# rtc_ds3231_shield.net
KiCad netlist of a schematic drawn in EAGLE
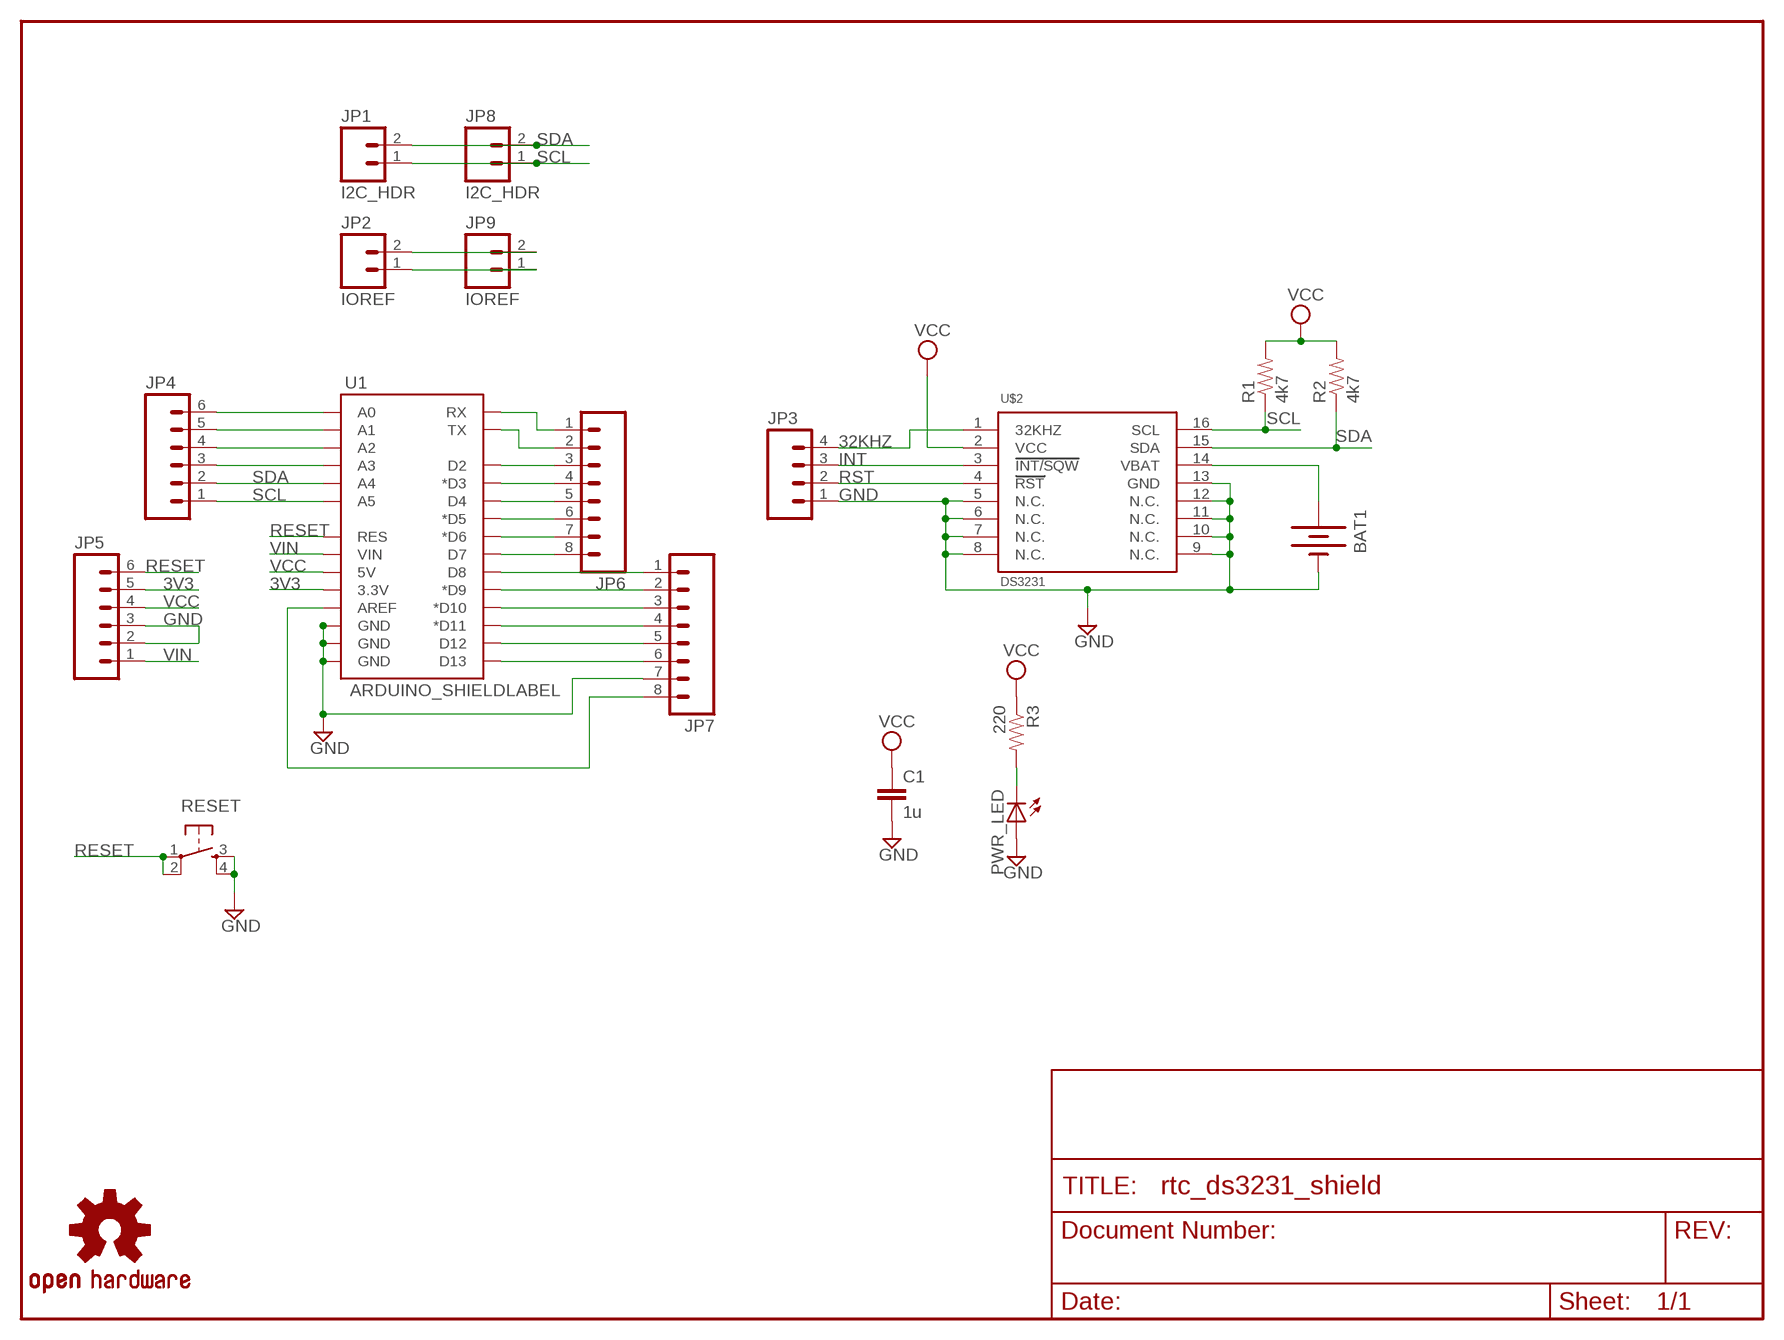
[diagram p0: schematic, sheet 1]

(export (version "E")
  (design (tool "Eeschema 10.0.6"))
  (components
    (comp (ref "BAT1")
      (value "BATTERY12MM")
      (footprint "eagle-import:BATTCON_12MM")
      (libsource (lib "eagle-import") (part "BATTERY12MM"))
    )
    (comp (ref "C1")
      (value "1u")
      (footprint "eagle-import:1206")
      (libsource (lib "eagle-import") (part "CAP1206"))
    )
    (comp (ref "JP1")
      (value "I2C_HDR")
      (footprint "eagle-import:1X02")
      (libsource (lib "eagle-import") (part "M02PTH"))
    )
    (comp (ref "JP2")
      (value "IOREF")
      (footprint "eagle-import:1X02")
      (libsource (lib "eagle-import") (part "M02PTH"))
    )
    (comp (ref "JP3")
      (value "M04PTH")
      (footprint "eagle-import:1X04")
      (libsource (lib "eagle-import") (part "M04PTH"))
    )
    (comp (ref "JP4")
      (value "M06SIP")
      (footprint "eagle-import:1X06")
      (libsource (lib "eagle-import") (part "M06SIP"))
    )
    (comp (ref "JP5")
      (value "M06SIP")
      (footprint "eagle-import:1X06")
      (libsource (lib "eagle-import") (part "M06SIP"))
    )
    (comp (ref "JP6")
      (value "M081X08")
      (footprint "eagle-import:1X08")
      (libsource (lib "eagle-import") (part "M081X08"))
    )
    (comp (ref "JP7")
      (value "M081X08")
      (footprint "eagle-import:1X08")
      (libsource (lib "eagle-import") (part "M081X08"))
    )
    (comp (ref "JP8")
      (value "I2C_HDR")
      (footprint "eagle-import:1X02")
      (libsource (lib "eagle-import") (part "M02PTH"))
    )
    (comp (ref "JP9")
      (value "IOREF")
      (footprint "eagle-import:1X02")
      (libsource (lib "eagle-import") (part "M02PTH"))
    )
    (comp (ref "PWR_LED")
      (value "LED1206")
      (footprint "eagle-import:LED-1206")
      (libsource (lib "eagle-import") (part "LED1206"))
    )
    (comp (ref "R1")
      (value "4k7")
      (footprint "eagle-import:1206")
      (libsource (lib "eagle-import") (part "RESISTOR1206"))
    )
    (comp (ref "R2")
      (value "4k7")
      (footprint "eagle-import:1206")
      (libsource (lib "eagle-import") (part "RESISTOR1206"))
    )
    (comp (ref "R3")
      (value "220")
      (footprint "eagle-import:1206")
      (libsource (lib "eagle-import") (part "RESISTOR1206"))
    )
    (comp (ref "RESET")
      (value "TAC_SWITCHSMD")
      (footprint "eagle-import:TACTILE_SWITCH_SMD")
      (libsource (lib "eagle-import") (part "TAC_SWITCHSMD"))
    )
    (comp (ref "U$2")
      (value "DS3231")
      (footprint "eagle-import:SO16L")
      (libsource (lib "eagle-import") (part "DS3231"))
    )
    (comp (ref "U$3")
      (value "OSHW-LOGOM")
      (footprint "eagle-import:OSHW-LOGO-M")
      (libsource (lib "eagle-import") (part "OSHW-LOGOM"))
    )
    (comp (ref "U1")
      (value "ARDUINO_SHIELDLABEL")
      (footprint "eagle-import:UNOR3_SHIELD")
      (libsource (lib "eagle-import") (part "ARDUINO_SHIELDLABEL"))
    )
  )
  (nets
    (net (code "1") (name "/3V3") (class "Default")
      (node (ref "JP5") (pin "5") (pinfunction "5_5") (pintype "passive"))
      (node (ref "U1") (pin "3.3V") (pinfunction "3.3V_3.3V") (pintype "bidirectional"))
    )
    (net (code "2") (name "/32KHZ") (class "Default")
      (node (ref "JP3") (pin "4") (pinfunction "4_4") (pintype "passive"))
      (node (ref "U$2") (pin "1") (pinfunction "32KHZ_1") (pintype "bidirectional"))
    )
    (net (code "3") (name "/INT") (class "Default")
      (node (ref "JP3") (pin "3") (pinfunction "3_3") (pintype "passive"))
      (node (ref "U$2") (pin "3") (pinfunction "INT/SQW_3") (pintype "bidirectional"))
    )
    (net (code "4") (name "/RESET") (class "Default")
      (node (ref "JP5") (pin "6") (pinfunction "6_6") (pintype "passive"))
      (node (ref "RESET") (pin "1") (pinfunction "1_1") (pintype "passive"))
      (node (ref "RESET") (pin "2") (pinfunction "2_2") (pintype "passive"))
      (node (ref "U1") (pin "RES") (pinfunction "RES_RES") (pintype "bidirectional"))
    )
    (net (code "5") (name "/RST") (class "Default")
      (node (ref "JP3") (pin "2") (pinfunction "2_2") (pintype "passive"))
      (node (ref "U$2") (pin "4") (pinfunction "RST_4") (pintype "bidirectional"))
    )
    (net (code "6") (name "/SCL") (class "Default")
      (node (ref "JP1") (pin "1") (pinfunction "1_1") (pintype "passive"))
      (node (ref "JP4") (pin "1") (pinfunction "1_1") (pintype "passive"))
      (node (ref "JP8") (pin "1") (pinfunction "1_1") (pintype "passive"))
      (node (ref "R1") (pin "1") (pinfunction "1_1") (pintype "passive"))
      (node (ref "U$2") (pin "16") (pinfunction "SCL_16") (pintype "bidirectional"))
      (node (ref "U1") (pin "A5") (pinfunction "A5_A5") (pintype "bidirectional"))
    )
    (net (code "7") (name "/SDA") (class "Default")
      (node (ref "JP1") (pin "2") (pinfunction "2_2") (pintype "passive"))
      (node (ref "JP4") (pin "2") (pinfunction "2_2") (pintype "passive"))
      (node (ref "JP8") (pin "2") (pinfunction "2_2") (pintype "passive"))
      (node (ref "R2") (pin "1") (pinfunction "1_1") (pintype "passive"))
      (node (ref "U$2") (pin "15") (pinfunction "SDA_15") (pintype "bidirectional"))
      (node (ref "U1") (pin "A4") (pinfunction "A4_A4") (pintype "bidirectional"))
    )
    (net (code "8") (name "/VIN") (class "Default")
      (node (ref "JP5") (pin "1") (pinfunction "1_1") (pintype "passive"))
      (node (ref "U1") (pin "VIN") (pinfunction "VIN_VIN") (pintype "bidirectional"))
    )
    (net (code "9") (name "GND") (class "Default")
      (node (ref "BAT1") (pin "GND") (pinfunction "-_GND") (pintype "power_in"))
      (node (ref "C1") (pin "2") (pinfunction "2_2") (pintype "passive"))
      (node (ref "JP3") (pin "1") (pinfunction "1_1") (pintype "passive"))
      (node (ref "JP5") (pin "2") (pinfunction "2_2") (pintype "passive"))
      (node (ref "JP5") (pin "3") (pinfunction "3_3") (pintype "passive"))
      (node (ref "JP7") (pin "7") (pinfunction "7_7") (pintype "passive"))
      (node (ref "PWR_LED") (pin "A") (pinfunction "A_A") (pintype "passive"))
      (node (ref "RESET") (pin "3") (pinfunction "3_3") (pintype "passive"))
      (node (ref "RESET") (pin "4") (pinfunction "4_4") (pintype "passive"))
      (node (ref "U$2") (pin "10") (pinfunction "N.C._10") (pintype "bidirectional"))
      (node (ref "U$2") (pin "11") (pinfunction "N.C._11") (pintype "bidirectional"))
      (node (ref "U$2") (pin "12") (pinfunction "N.C._12") (pintype "bidirectional"))
      (node (ref "U$2") (pin "13") (pinfunction "GND_13") (pintype "power_in"))
      (node (ref "U$2") (pin "5") (pinfunction "N.C._5") (pintype "bidirectional"))
      (node (ref "U$2") (pin "6") (pinfunction "N.C._6") (pintype "bidirectional"))
      (node (ref "U$2") (pin "7") (pinfunction "N.C._7") (pintype "bidirectional"))
      (node (ref "U$2") (pin "8") (pinfunction "N.C._8") (pintype "bidirectional"))
      (node (ref "U$2") (pin "9") (pinfunction "N.C._9") (pintype "bidirectional"))
      (node (ref "U1") (pin "GND@0") (pinfunction "GND_GND@0") (pintype "bidirectional"))
      (node (ref "U1") (pin "GND@1") (pinfunction "GND_GND@1") (pintype "bidirectional"))
      (node (ref "U1") (pin "GND@2") (pinfunction "GND_GND@2") (pintype "bidirectional"))
    )
    (net (code "10") (name "Net-(BAT1-+)") (class "Default")
      (node (ref "BAT1") (pin "PWR@2") (pinfunction "+_PWR@2") (pintype "power_in"))
      (node (ref "U$2") (pin "14") (pinfunction "VBAT_14") (pintype "power_in"))
    )
    (net (code "11") (name "Net-(JP2-Pad1)") (class "Default")
      (node (ref "JP2") (pin "1") (pinfunction "1_1") (pintype "passive"))
      (node (ref "JP9") (pin "1") (pinfunction "1_1") (pintype "passive"))
    )
    (net (code "12") (name "Net-(JP2-Pad2)") (class "Default")
      (node (ref "JP2") (pin "2") (pinfunction "2_2") (pintype "passive"))
      (node (ref "JP9") (pin "2") (pinfunction "2_2") (pintype "passive"))
    )
    (net (code "13") (name "Net-(JP4-Pad3)") (class "Default")
      (node (ref "JP4") (pin "3") (pinfunction "3_3") (pintype "passive"))
      (node (ref "U1") (pin "A3") (pinfunction "A3_A3") (pintype "bidirectional"))
    )
    (net (code "14") (name "Net-(JP4-Pad4)") (class "Default")
      (node (ref "JP4") (pin "4") (pinfunction "4_4") (pintype "passive"))
      (node (ref "U1") (pin "A2") (pinfunction "A2_A2") (pintype "bidirectional"))
    )
    (net (code "15") (name "Net-(JP4-Pad5)") (class "Default")
      (node (ref "JP4") (pin "5") (pinfunction "5_5") (pintype "passive"))
      (node (ref "U1") (pin "A1") (pinfunction "A1_A1") (pintype "bidirectional"))
    )
    (net (code "16") (name "Net-(JP4-Pad6)") (class "Default")
      (node (ref "JP4") (pin "6") (pinfunction "6_6") (pintype "passive"))
      (node (ref "U1") (pin "A0") (pinfunction "A0_A0") (pintype "bidirectional"))
    )
    (net (code "17") (name "Net-(JP6-Pad1)") (class "Default")
      (node (ref "JP6") (pin "1") (pinfunction "1_1") (pintype "passive"))
      (node (ref "U1") (pin "RX") (pinfunction "RX_RX") (pintype "bidirectional"))
    )
    (net (code "18") (name "Net-(JP6-Pad2)") (class "Default")
      (node (ref "JP6") (pin "2") (pinfunction "2_2") (pintype "passive"))
      (node (ref "U1") (pin "TX") (pinfunction "TX_TX") (pintype "bidirectional"))
    )
    (net (code "19") (name "Net-(JP6-Pad3)") (class "Default")
      (node (ref "JP6") (pin "3") (pinfunction "3_3") (pintype "passive"))
      (node (ref "U1") (pin "D2") (pinfunction "D2_D2") (pintype "bidirectional"))
    )
    (net (code "20") (name "Net-(JP6-Pad5)") (class "Default")
      (node (ref "JP6") (pin "5") (pinfunction "5_5") (pintype "passive"))
      (node (ref "U1") (pin "D4") (pinfunction "D4_D4") (pintype "bidirectional"))
    )
    (net (code "21") (name "Net-(JP6-Pad8)") (class "Default")
      (node (ref "JP6") (pin "8") (pinfunction "8_8") (pintype "passive"))
      (node (ref "U1") (pin "D7") (pinfunction "D7_D7") (pintype "bidirectional"))
    )
    (net (code "22") (name "Net-(JP7-Pad1)") (class "Default")
      (node (ref "JP7") (pin "1") (pinfunction "1_1") (pintype "passive"))
      (node (ref "U1") (pin "D8") (pinfunction "D8_D8") (pintype "bidirectional"))
    )
    (net (code "23") (name "Net-(JP7-Pad5)") (class "Default")
      (node (ref "JP7") (pin "5") (pinfunction "5_5") (pintype "passive"))
      (node (ref "U1") (pin "D12") (pinfunction "D12_D12") (pintype "bidirectional"))
    )
    (net (code "24") (name "Net-(JP7-Pad6)") (class "Default")
      (node (ref "JP7") (pin "6") (pinfunction "6_6") (pintype "passive"))
      (node (ref "U1") (pin "D13") (pinfunction "D13_D13") (pintype "bidirectional"))
    )
    (net (code "25") (name "Net-(JP7-Pad8)") (class "Default")
      (node (ref "JP7") (pin "8") (pinfunction "8_8") (pintype "passive"))
      (node (ref "U1") (pin "AREF") (pinfunction "AREF_AREF") (pintype "bidirectional"))
    )
    (net (code "26") (name "Net-(PWR_LED-PadC)") (class "Default")
      (node (ref "PWR_LED") (pin "C") (pinfunction "C_C") (pintype "passive"))
      (node (ref "R3") (pin "2") (pinfunction "2_2") (pintype "passive"))
    )
    (net (code "27") (name "Net-(U1-*D3)") (class "Default")
      (node (ref "JP6") (pin "4") (pinfunction "4_4") (pintype "passive"))
      (node (ref "U1") (pin "D3") (pinfunction "*D3_D3") (pintype "bidirectional"))
    )
    (net (code "28") (name "Net-(U1-*D5)") (class "Default")
      (node (ref "JP6") (pin "6") (pinfunction "6_6") (pintype "passive"))
      (node (ref "U1") (pin "D5") (pinfunction "*D5_D5") (pintype "bidirectional"))
    )
    (net (code "29") (name "Net-(U1-*D6)") (class "Default")
      (node (ref "JP6") (pin "7") (pinfunction "7_7") (pintype "passive"))
      (node (ref "U1") (pin "D6") (pinfunction "*D6_D6") (pintype "bidirectional"))
    )
    (net (code "30") (name "Net-(U1-*D9)") (class "Default")
      (node (ref "JP7") (pin "2") (pinfunction "2_2") (pintype "passive"))
      (node (ref "U1") (pin "D9") (pinfunction "*D9_D9") (pintype "bidirectional"))
    )
    (net (code "31") (name "Net-(U1-*D10)") (class "Default")
      (node (ref "JP7") (pin "3") (pinfunction "3_3") (pintype "passive"))
      (node (ref "U1") (pin "D10") (pinfunction "*D10_D10") (pintype "bidirectional"))
    )
    (net (code "32") (name "Net-(U1-*D11)") (class "Default")
      (node (ref "JP7") (pin "4") (pinfunction "4_4") (pintype "passive"))
      (node (ref "U1") (pin "D11") (pinfunction "*D11_D11") (pintype "bidirectional"))
    )
    (net (code "33") (name "VCC") (class "Default")
      (node (ref "C1") (pin "1") (pinfunction "1_1") (pintype "passive"))
      (node (ref "JP5") (pin "4") (pinfunction "4_4") (pintype "passive"))
      (node (ref "R1") (pin "2") (pinfunction "2_2") (pintype "passive"))
      (node (ref "R2") (pin "2") (pinfunction "2_2") (pintype "passive"))
      (node (ref "R3") (pin "1") (pinfunction "1_1") (pintype "passive"))
      (node (ref "U$2") (pin "2") (pinfunction "VCC_2") (pintype "power_in"))
      (node (ref "U1") (pin "5V") (pinfunction "5V_5V") (pintype "bidirectional"))
    )
  )
)
